# Sheet1.net
KiCad netlist of a schematic drawn in Altium Designer
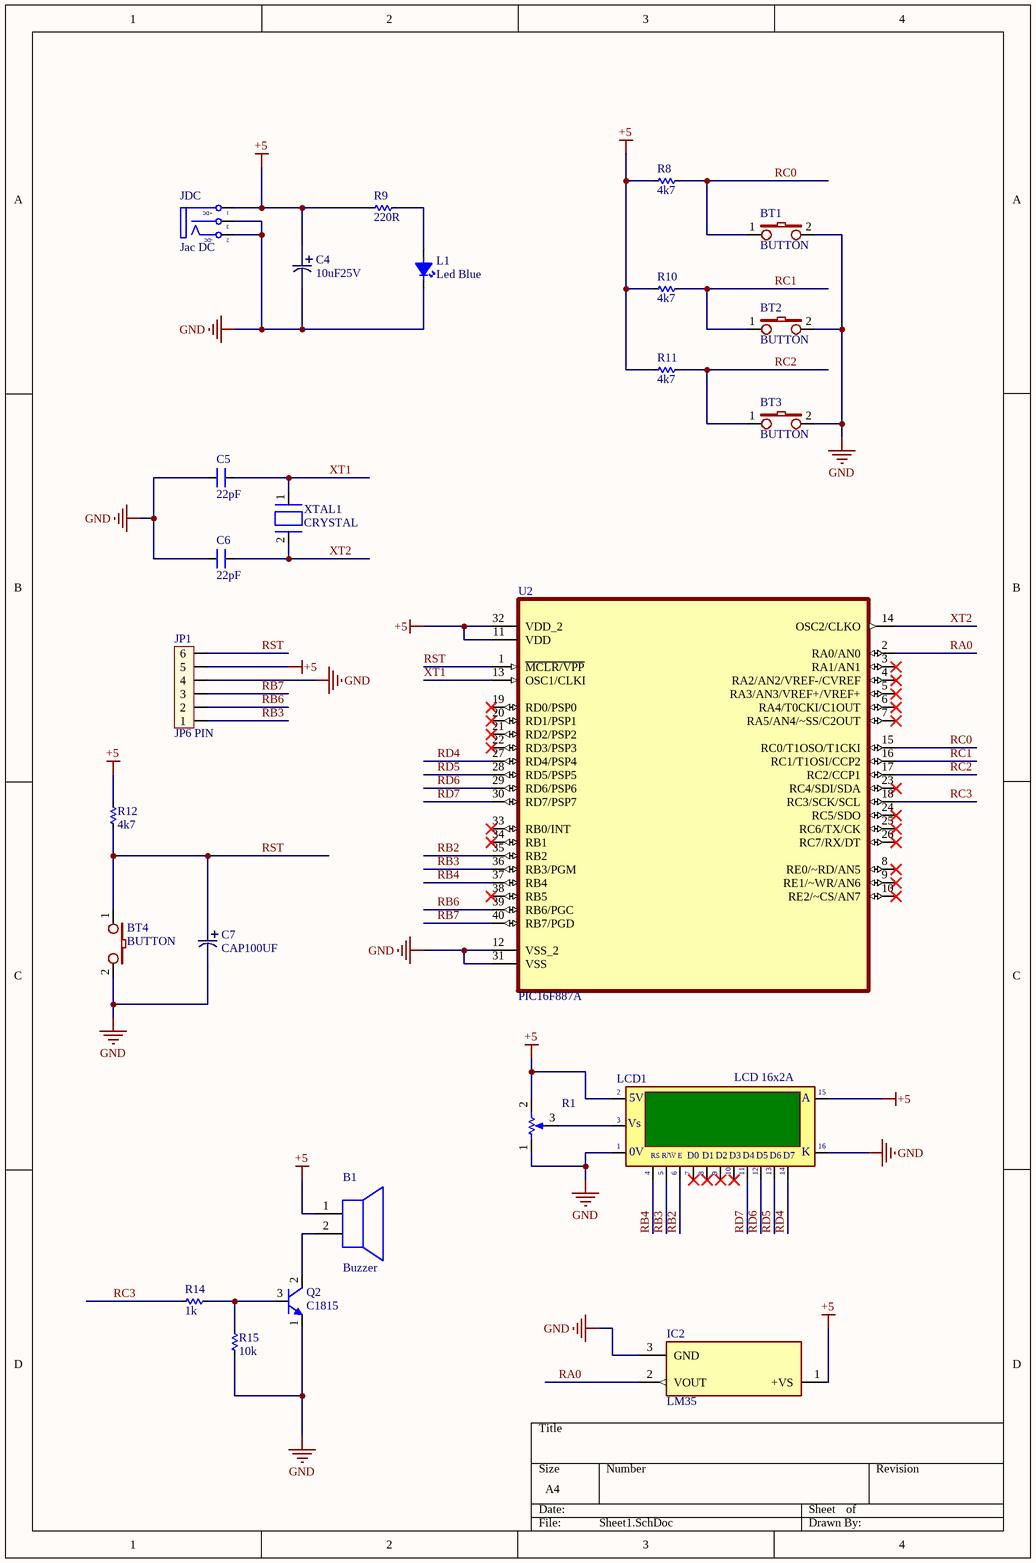
[diagram p0: Sheet1.SchDoc]

(export (version "E")
  (design (tool "Eeschema 10.0.6"))
  (components
    (comp (ref "B1") (value "Buzzer") (footprint "Buzzer") (libsource (lib "BOYCODON_123") (part "Buzzer")))
    (comp (ref "BT1") (value "BUTTON") (footprint "BUTTON") (libsource (lib "BOYCODON_123") (part "BUTTON")))
    (comp (ref "BT2") (value "BUTTON") (footprint "BUTTON") (libsource (lib "BOYCODON_123") (part "BUTTON")))
    (comp (ref "BT3") (value "BUTTON") (footprint "BUTTON") (libsource (lib "BOYCODON_123") (part "BUTTON")))
    (comp (ref "BT4") (value "BUTTON") (footprint "BUTTON") (libsource (lib "BOYCODON_123") (part "BUTTON")))
    (comp (ref "C4")
      (value "10uF25V")
      (footprint "CAP10UF25V")
      (description "CAP 10UF 25V 4W7H2P")
      (libsource (lib "BOYCODON_123") (part "CAP 10UF25V"))
    )
    (comp (ref "C5")
      (value "22pF")
      (footprint "CN4 5MMP")
      (libsource (lib "BOYCODON_123") (part "CAP CERAMIC"))
    )
    (comp (ref "C6")
      (value "22pF")
      (footprint "CN4 5MMP")
      (libsource (lib "BOYCODON_123") (part "CAP CERAMIC"))
    )
    (comp (ref "C7")
      (value "CAP100UF")
      (footprint "CAP 100UF 16V")
      (description "CAP100UF 16V 2P")
      (libsource (lib "BOYCODON_123") (part "CAP100UF16V"))
    )
    (comp (ref "IC2") (value "LM35") (footprint "LM35") (libsource (lib "BOYCODON_123") (part "LM35")))
    (comp (ref "JDC")
      (value "Jac DC")
      (footprint "DC-IN")
      (description "Jac DC input")
      (libsource (lib "BOYCODON_123") (part "DCIN"))
    )
    (comp (ref "JP1") (value "JP6 PIN") (footprint "JP_6PIN") (libsource (lib "BOYCODON_123") (part "JP6")))
    (comp (ref "L1")
      (value "Led Blue")
      (footprint "Led__Blue_t/h_5mm")
      (libsource (lib "BOYCODON_123") (part "Led Blue"))
    )
    (comp (ref "LCD1")
      (value "LCD 16x2A")
      (footprint "LCD1602")
      (description "LCD dipslay 16 char, 2 line")
      (libsource (lib "BOYCODON_123") (part "LCD16x2A"))
    )
    (comp (ref "Q2")
      (value "C1815")
      (footprint "2SC1815")
      (description "Trans NPN 50V 150mA TO-92")
      (libsource (lib "BOYCODON_123") (part "TRANS_NPN_C1815"))
    )
    (comp (ref "R1")
      (value "POT - cuc ao")
      (footprint "POT - cuc ao 10k")
      (description "10k")
      (libsource (lib "BOYCODON_123") (part "POT - cuc ao"))
    )
    (comp (ref "R8")
      (value "4k7")
      (footprint "R025W_AX04")
      (description "Res")
      (fields
        (field (name "MANUFACTURER") "Generic Components")
        (field (name "PUBLISHER") "Altium Hobart Technology Centre")
      )
      (libsource (lib "BOYCODON_123") (part "Res"))
    )
    (comp (ref "R9")
      (value "220R")
      (footprint "R025W_AX04")
      (description "Res")
      (fields
        (field (name "MANUFACTURER") "Generic Components")
        (field (name "PUBLISHER") "Altium Hobart Technology Centre")
      )
      (libsource (lib "BOYCODON_123") (part "Res"))
    )
    (comp (ref "R10")
      (value "4k7")
      (footprint "R025W_AX04")
      (description "Res")
      (fields
        (field (name "MANUFACTURER") "Generic Components")
        (field (name "PUBLISHER") "Altium Hobart Technology Centre")
      )
      (libsource (lib "BOYCODON_123") (part "Res"))
    )
    (comp (ref "R11")
      (value "4k7")
      (footprint "R025W_AX04")
      (description "Res")
      (fields
        (field (name "MANUFACTURER") "Generic Components")
        (field (name "PUBLISHER") "Altium Hobart Technology Centre")
      )
      (libsource (lib "BOYCODON_123") (part "Res"))
    )
    (comp (ref "R12")
      (value "4k7")
      (footprint "R025W_AX04")
      (description "Res")
      (fields
        (field (name "MANUFACTURER") "Generic Components")
        (field (name "PUBLISHER") "Altium Hobart Technology Centre")
      )
      (libsource (lib "BOYCODON_123") (part "Res"))
    )
    (comp (ref "R14")
      (value "1k")
      (footprint "R025W_AX04")
      (description "Res")
      (fields
        (field (name "MANUFACTURER") "Generic Components")
        (field (name "PUBLISHER") "Altium Hobart Technology Centre")
      )
      (libsource (lib "BOYCODON_123") (part "Res"))
    )
    (comp (ref "R15")
      (value "10k")
      (footprint "R025W_AX04")
      (description "Res")
      (fields
        (field (name "MANUFACTURER") "Generic Components")
        (field (name "PUBLISHER") "Altium Hobart Technology Centre")
      )
      (libsource (lib "BOYCODON_123") (part "Res"))
    )
    (comp (ref "U2")
      (value "PIC16F887A")
      (footprint "PIC16F877A")
      (description "PIC PIC16F Microcontroller IC 8-Bit 20MHz 14KB (8K x 14) FLASH 44-TQFP (10x10)")
      (libsource (lib "BOYCODON_123") (part "PIC16F887A"))
    )
    (comp (ref "XTAL1")
      (value "CRYSTAL")
      (footprint "Crystal")
      (libsource (lib "BOYCODON_123") (part "CRYSTAL"))
    )
  )
  (nets
    (net (code "1") (name "+5") (class "Default")
      (node (ref "B1") (pin "1") (pinfunction "+_1") (pintype "passive"))
      (node (ref "C4") (pin "1") (pinfunction "1_1") (pintype "passive"))
      (node (ref "IC2") (pin "1") (pinfunction "+VS_1") (pintype "power_in"))
      (node (ref "JDC") (pin "1") (pinfunction "T_1") (pintype "passive"))
      (node (ref "JP1") (pin "5") (pinfunction "5_5") (pintype "passive"))
      (node (ref "LCD1") (pin "15") (pinfunction "A_15") (pintype "passive"))
      (node (ref "LCD1") (pin "2") (pinfunction "VDD_2") (pintype "passive"))
      (node (ref "R1") (pin "2") (pinfunction "BOT_2") (pintype "passive"))
      (node (ref "R10") (pin "1") (pinfunction "1_1") (pintype "passive"))
      (node (ref "R11") (pin "1") (pinfunction "1_1") (pintype "passive"))
      (node (ref "R12") (pin "1") (pinfunction "1_1") (pintype "passive"))
      (node (ref "R8") (pin "1") (pinfunction "1_1") (pintype "passive"))
      (node (ref "R9") (pin "2") (pinfunction "2_2") (pintype "passive"))
      (node (ref "U2") (pin "11") (pinfunction "VDD_11") (pintype "power_in"))
      (node (ref "U2") (pin "32") (pinfunction "VDD_2_32") (pintype "power_in"))
    )
    (net (code "2") (name "/RA0") (class "Default")
      (node (ref "IC2") (pin "2") (pinfunction "VOUT_2") (pintype "output"))
      (node (ref "U2") (pin "2") (pinfunction "RA0/AN0_2") (pintype "bidirectional"))
    )
    (net (code "3") (name "/RB2") (class "Default")
      (node (ref "LCD1") (pin "6") (pinfunction "~{EN}_6") (pintype "passive"))
      (node (ref "U2") (pin "35") (pinfunction "RB2_35") (pintype "bidirectional"))
    )
    (net (code "4") (name "/RB3") (class "Default")
      (node (ref "JP1") (pin "1") (pinfunction "1_1") (pintype "passive"))
      (node (ref "LCD1") (pin "5") (pinfunction "R/~{W}_5") (pintype "passive"))
      (node (ref "U2") (pin "36") (pinfunction "RB3/PGM_36") (pintype "bidirectional"))
    )
    (net (code "5") (name "/RB4") (class "Default")
      (node (ref "LCD1") (pin "4") (pinfunction "RS_4") (pintype "passive"))
      (node (ref "U2") (pin "37") (pinfunction "RB4_37") (pintype "bidirectional"))
    )
    (net (code "6") (name "/RB6") (class "Default")
      (node (ref "JP1") (pin "2") (pinfunction "2_2") (pintype "passive"))
      (node (ref "U2") (pin "39") (pinfunction "RB6/PGC_39") (pintype "bidirectional"))
    )
    (net (code "7") (name "/RB7") (class "Default")
      (node (ref "JP1") (pin "3") (pinfunction "3_3") (pintype "passive"))
      (node (ref "U2") (pin "40") (pinfunction "RB7/PGD_40") (pintype "bidirectional"))
    )
    (net (code "8") (name "/RC0") (class "Default")
      (node (ref "BT1") (pin "1") (pinfunction "1_1") (pintype "passive"))
      (node (ref "R8") (pin "2") (pinfunction "2_2") (pintype "passive"))
      (node (ref "U2") (pin "15") (pinfunction "RC0/T1OSO/T1CKI_15") (pintype "bidirectional"))
    )
    (net (code "9") (name "/RC1") (class "Default")
      (node (ref "BT2") (pin "1") (pinfunction "1_1") (pintype "passive"))
      (node (ref "R10") (pin "2") (pinfunction "2_2") (pintype "passive"))
      (node (ref "U2") (pin "16") (pinfunction "RC1/T1OSI/CCP2_16") (pintype "bidirectional"))
    )
    (net (code "10") (name "/RC2") (class "Default")
      (node (ref "BT3") (pin "1") (pinfunction "1_1") (pintype "passive"))
      (node (ref "R11") (pin "2") (pinfunction "2_2") (pintype "passive"))
      (node (ref "U2") (pin "17") (pinfunction "RC2/CCP1_17") (pintype "bidirectional"))
    )
    (net (code "11") (name "/RC3") (class "Default")
      (node (ref "R14") (pin "1") (pinfunction "1_1") (pintype "passive"))
      (node (ref "U2") (pin "18") (pinfunction "RC3/SCK/SCL_18") (pintype "bidirectional"))
    )
    (net (code "12") (name "/RD4") (class "Default")
      (node (ref "LCD1") (pin "14") (pinfunction "D7_14") (pintype "passive"))
      (node (ref "U2") (pin "27") (pinfunction "RD4/PSP4_27") (pintype "bidirectional"))
    )
    (net (code "13") (name "/RD5") (class "Default")
      (node (ref "LCD1") (pin "13") (pinfunction "D6_13") (pintype "passive"))
      (node (ref "U2") (pin "28") (pinfunction "RD5/PSP5_28") (pintype "bidirectional"))
    )
    (net (code "14") (name "/RD6") (class "Default")
      (node (ref "LCD1") (pin "12") (pinfunction "D5_12") (pintype "passive"))
      (node (ref "U2") (pin "29") (pinfunction "RD6/PSP6_29") (pintype "bidirectional"))
    )
    (net (code "15") (name "/RD7") (class "Default")
      (node (ref "LCD1") (pin "11") (pinfunction "D4_11") (pintype "passive"))
      (node (ref "U2") (pin "30") (pinfunction "RD7/PSP7_30") (pintype "bidirectional"))
    )
    (net (code "16") (name "/RST") (class "Default")
      (node (ref "BT4") (pin "1") (pinfunction "1_1") (pintype "passive"))
      (node (ref "C7") (pin "1") (pinfunction "1_1") (pintype "passive"))
      (node (ref "JP1") (pin "6") (pinfunction "6_6") (pintype "passive"))
      (node (ref "R12") (pin "2") (pinfunction "2_2") (pintype "passive"))
      (node (ref "U2") (pin "1") (pinfunction "~{MCLR/VPP}_1") (pintype "input"))
    )
    (net (code "17") (name "/XT1") (class "Default")
      (node (ref "C5") (pin "1") (pinfunction "1_1") (pintype "passive"))
      (node (ref "U2") (pin "13") (pinfunction "OSC1/CLKI_13") (pintype "input"))
      (node (ref "XTAL1") (pin "1") (pinfunction "1_1") (pintype "passive"))
    )
    (net (code "18") (name "/XT2") (class "Default")
      (node (ref "C6") (pin "2") (pinfunction "2_2") (pintype "passive"))
      (node (ref "U2") (pin "14") (pinfunction "OSC2/CLKO_14") (pintype "output"))
      (node (ref "XTAL1") (pin "2") (pinfunction "2_2") (pintype "passive"))
    )
    (net (code "19") (name "GND") (class "Default")
      (node (ref "BT1") (pin "2") (pinfunction "2_2") (pintype "passive"))
      (node (ref "BT2") (pin "2") (pinfunction "2_2") (pintype "passive"))
      (node (ref "BT3") (pin "2") (pinfunction "2_2") (pintype "passive"))
      (node (ref "BT4") (pin "2") (pinfunction "2_2") (pintype "passive"))
      (node (ref "C4") (pin "2") (pinfunction "2_2") (pintype "passive"))
      (node (ref "C5") (pin "2") (pinfunction "2_2") (pintype "passive"))
      (node (ref "C6") (pin "1") (pinfunction "1_1") (pintype "passive"))
      (node (ref "C7") (pin "2") (pinfunction "2_2") (pintype "passive"))
      (node (ref "IC2") (pin "3") (pinfunction "GND_3") (pintype "power_in"))
      (node (ref "JDC") (pin "2") (pinfunction "TN_2") (pintype "passive"))
      (node (ref "JDC") (pin "3") (pinfunction "S_3") (pintype "power_in"))
      (node (ref "JP1") (pin "4") (pinfunction "4_4") (pintype "passive"))
      (node (ref "L1") (pin "2") (pinfunction "K_2") (pintype "passive"))
      (node (ref "LCD1") (pin "1") (pinfunction "GND_1") (pintype "passive"))
      (node (ref "LCD1") (pin "16") (pinfunction "K_16") (pintype "passive"))
      (node (ref "Q2") (pin "1") (pinfunction "E_1") (pintype "passive"))
      (node (ref "R1") (pin "1") (pinfunction "TOP_1") (pintype "passive"))
      (node (ref "R15") (pin "1") (pinfunction "1_1") (pintype "passive"))
      (node (ref "U2") (pin "12") (pinfunction "VSS_2_12") (pintype "power_in"))
      (node (ref "U2") (pin "31") (pinfunction "VSS_31") (pintype "power_in"))
    )
    (net (code "20") (name "Net-(B1--)") (class "Default")
      (node (ref "B1") (pin "2") (pinfunction "-_2") (pintype "passive"))
      (node (ref "Q2") (pin "2") (pinfunction "C_2") (pintype "passive"))
    )
    (net (code "21") (name "Net-(L1-A)") (class "Default")
      (node (ref "L1") (pin "1") (pinfunction "A_1") (pintype "passive"))
      (node (ref "R9") (pin "1") (pinfunction "1_1") (pintype "passive"))
    )
    (net (code "22") (name "Net-(LCD1-VEE)") (class "Default")
      (node (ref "LCD1") (pin "3") (pinfunction "VEE_3") (pintype "passive"))
      (node (ref "R1") (pin "3") (pinfunction "TAP_3") (pintype "passive"))
    )
    (net (code "23") (name "Net-(Q2-B)") (class "Default")
      (node (ref "Q2") (pin "3") (pinfunction "B_3") (pintype "passive"))
      (node (ref "R14") (pin "2") (pinfunction "2_2") (pintype "passive"))
      (node (ref "R15") (pin "2") (pinfunction "2_2") (pintype "passive"))
    )
    (net (code "24") (name "unconnected-(LCD1-D0-Pad7)") (class "Default")
      (node (ref "LCD1") (pin "7") (pinfunction "D0_7") (pintype "passive+no_connect"))
    )
    (net (code "25") (name "unconnected-(LCD1-D1-Pad8)") (class "Default")
      (node (ref "LCD1") (pin "8") (pinfunction "D1_8") (pintype "passive+no_connect"))
    )
    (net (code "26") (name "unconnected-(LCD1-D2-Pad9)") (class "Default")
      (node (ref "LCD1") (pin "9") (pinfunction "D2_9") (pintype "passive+no_connect"))
    )
    (net (code "27") (name "unconnected-(LCD1-D3-Pad10)") (class "Default")
      (node (ref "LCD1") (pin "10") (pinfunction "D3_10") (pintype "passive+no_connect"))
    )
    (net (code "28") (name "unconnected-(U2-RA1{slash}AN1-Pad3)") (class "Default")
      (node (ref "U2") (pin "3") (pinfunction "RA1/AN1_3") (pintype "bidirectional+no_connect"))
    )
    (net (code "29") (name "unconnected-(U2-RA2{slash}AN2{slash}VREF-{slash}CVREF-Pad4)") (class "Default")
      (node (ref "U2") (pin "4") (pinfunction "RA2/AN2/VREF-/CVREF_4") (pintype "bidirectional+no_connect"))
    )
    (net (code "30") (name "unconnected-(U2-RA3{slash}AN3{slash}VREF+{slash}VREF+-Pad5)") (class "Default")
      (node (ref "U2") (pin "5") (pinfunction "RA3/AN3/VREF+/VREF+_5") (pintype "bidirectional+no_connect"))
    )
    (net (code "31") (name "unconnected-(U2-RA4{slash}T0CKI{slash}C1OUT-Pad6)") (class "Default")
      (node (ref "U2") (pin "6") (pinfunction "RA4/T0CKI/C1OUT_6") (pintype "bidirectional+no_connect"))
    )
    (net (code "32") (name "unconnected-(U2-RA5{slash}AN4{slash}~SS{slash}C2OUT-Pad7)") (class "Default")
      (node (ref "U2") (pin "7") (pinfunction "RA5/AN4/~SS/C2OUT_7") (pintype "bidirectional+no_connect"))
    )
    (net (code "33") (name "unconnected-(U2-RB0{slash}INT-Pad33)") (class "Default")
      (node (ref "U2") (pin "33") (pinfunction "RB0/INT_33") (pintype "bidirectional+no_connect"))
    )
    (net (code "34") (name "unconnected-(U2-RB1-Pad34)") (class "Default")
      (node (ref "U2") (pin "34") (pinfunction "RB1_34") (pintype "bidirectional+no_connect"))
    )
    (net (code "35") (name "unconnected-(U2-RB5-Pad38)") (class "Default")
      (node (ref "U2") (pin "38") (pinfunction "RB5_38") (pintype "bidirectional+no_connect"))
    )
    (net (code "36") (name "unconnected-(U2-RC4{slash}SDI{slash}SDA-Pad23)") (class "Default")
      (node (ref "U2") (pin "23") (pinfunction "RC4/SDI/SDA_23") (pintype "bidirectional+no_connect"))
    )
    (net (code "37") (name "unconnected-(U2-RC5{slash}SDO-Pad24)") (class "Default")
      (node (ref "U2") (pin "24") (pinfunction "RC5/SDO_24") (pintype "bidirectional+no_connect"))
    )
    (net (code "38") (name "unconnected-(U2-RC6{slash}TX{slash}CK-Pad25)") (class "Default")
      (node (ref "U2") (pin "25") (pinfunction "RC6/TX/CK_25") (pintype "bidirectional+no_connect"))
    )
    (net (code "39") (name "unconnected-(U2-RC7{slash}RX{slash}DT-Pad26)") (class "Default")
      (node (ref "U2") (pin "26") (pinfunction "RC7/RX/DT_26") (pintype "bidirectional+no_connect"))
    )
    (net (code "40") (name "unconnected-(U2-RD0{slash}PSP0-Pad19)") (class "Default")
      (node (ref "U2") (pin "19") (pinfunction "RD0/PSP0_19") (pintype "bidirectional+no_connect"))
    )
    (net (code "41") (name "unconnected-(U2-RD1{slash}PSP1-Pad20)") (class "Default")
      (node (ref "U2") (pin "20") (pinfunction "RD1/PSP1_20") (pintype "bidirectional+no_connect"))
    )
    (net (code "42") (name "unconnected-(U2-RD2{slash}PSP2-Pad21)") (class "Default")
      (node (ref "U2") (pin "21") (pinfunction "RD2/PSP2_21") (pintype "bidirectional+no_connect"))
    )
    (net (code "43") (name "unconnected-(U2-RD3{slash}PSP3-Pad22)") (class "Default")
      (node (ref "U2") (pin "22") (pinfunction "RD3/PSP3_22") (pintype "bidirectional+no_connect"))
    )
    (net (code "44") (name "unconnected-(U2-RE0{slash}~RD{slash}AN5-Pad8)") (class "Default")
      (node (ref "U2") (pin "8") (pinfunction "RE0/~RD/AN5_8") (pintype "bidirectional+no_connect"))
    )
    (net (code "45") (name "unconnected-(U2-RE1{slash}~WR{slash}AN6-Pad9)") (class "Default")
      (node (ref "U2") (pin "9") (pinfunction "RE1/~WR/AN6_9") (pintype "bidirectional+no_connect"))
    )
    (net (code "46") (name "unconnected-(U2-RE2{slash}~CS{slash}AN7-Pad10)") (class "Default")
      (node (ref "U2") (pin "10") (pinfunction "RE2/~CS/AN7_10") (pintype "bidirectional+no_connect"))
    )
  )
)
